# 1-Schematic_picaxe-SMALL.net
KiCad netlist of a schematic drawn in EasyEDA
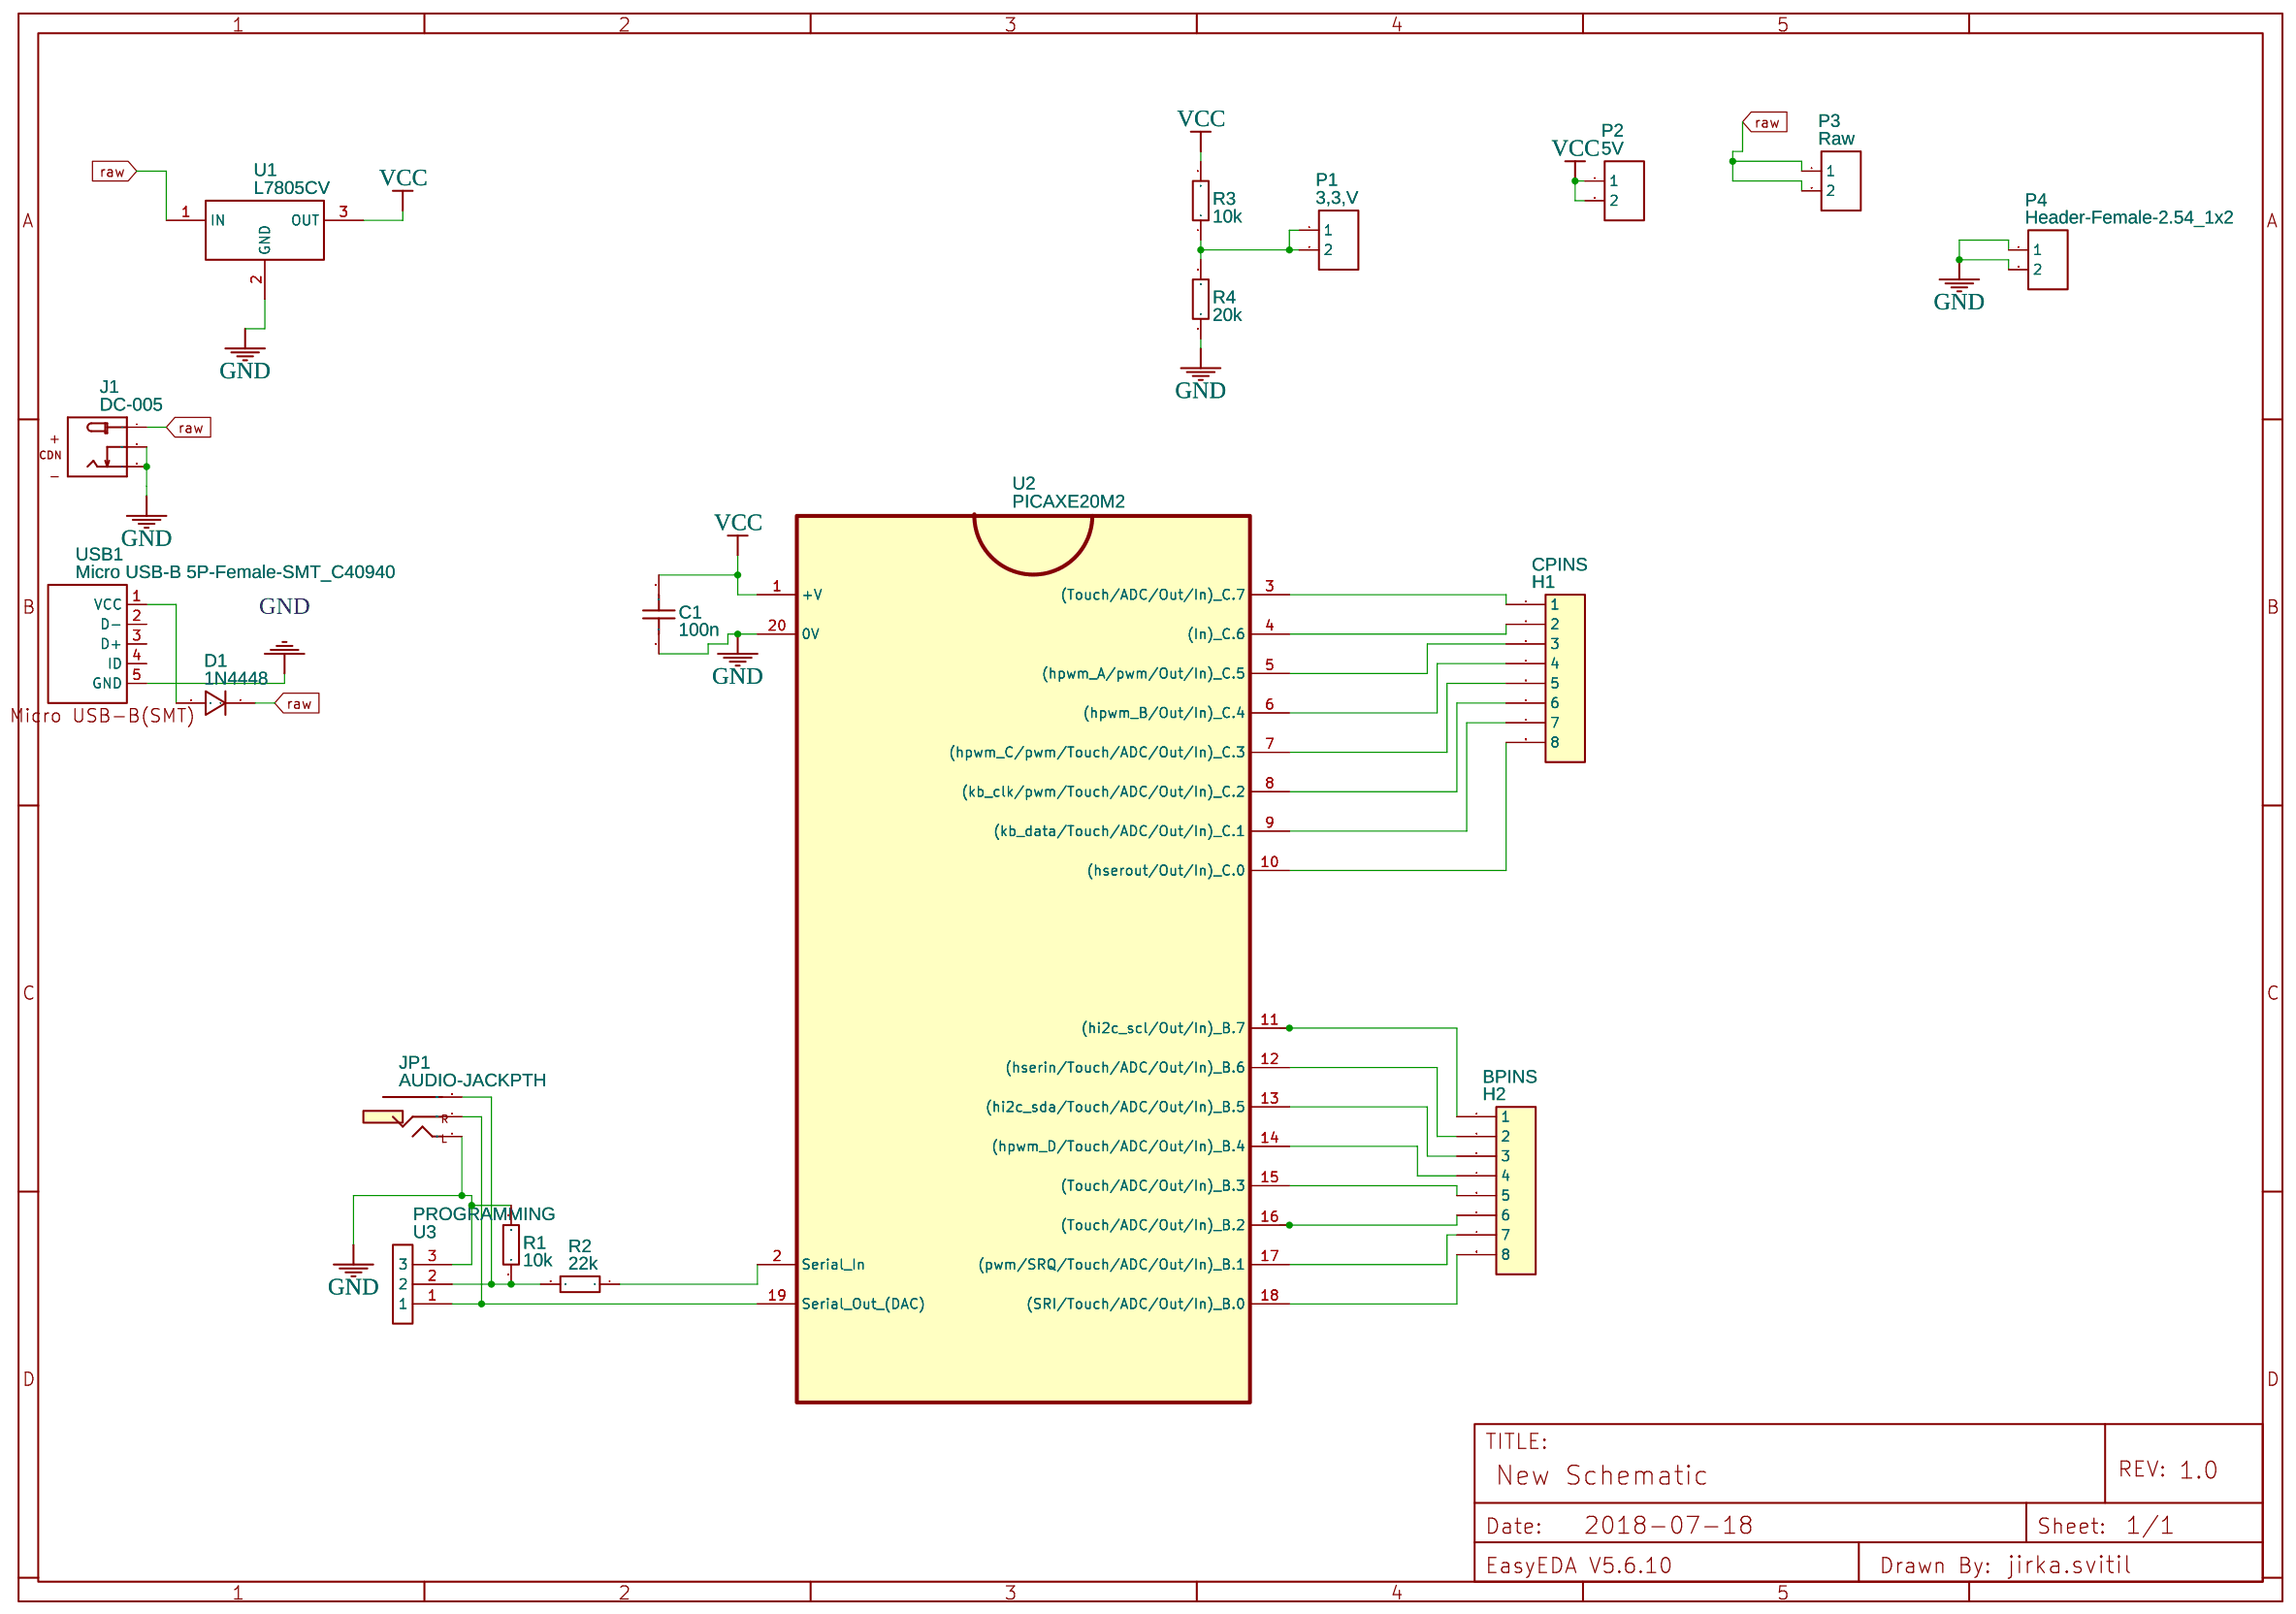
[diagram p0: schematic sheet]

(export (version "E")
  (design (tool "Eeschema 10.0.6"))
  (components
    (comp (ref "BPINS")
      (value "H2")
      (fields (field (name "BOM_Manufacturer Part") "?"))
      (libsource (lib "") (part "Unknown_740_580"))
    )
    (comp (ref "C1")
      (value "100n")
      (fields (field (name "BOM_Manufacturer Part") "?"))
      (libsource (lib "") (part "Cap_RAD-0.1_US"))
    )
    (comp (ref "CPINS")
      (value "H1")
      (fields (field (name "BOM_Manufacturer Part") "?"))
      (libsource (lib "") (part "Unknown_765_320"))
    )
    (comp (ref "D1") (value "1N4448") (libsource (lib "") (part "Unknown_100_350")))
    (comp (ref "J1") (value "DC-005") (libsource (lib "") (part "Unknown_40_220")))
    (comp (ref "JP1")
      (value "AUDIO-JACKPTH")
      (fields (field (name "BOM_Manufacturer Part") "?"))
      (libsource (lib "") (part "Unknown_205_560"))
    )
    (comp (ref "P1")
      (value "3,3,V")
      (fields (field (name "BOM_Manufacturer Part") "2.54-1*2PFemale"))
      (libsource (lib "") (part "Unknown_665_115"))
    )
    (comp (ref "P2")
      (value "5V")
      (fields (field (name "BOM_Manufacturer Part") "2.54-1*2PFemale"))
      (libsource (lib "") (part "Unknown_810_90"))
    )
    (comp (ref "P3")
      (value "Raw")
      (fields (field (name "BOM_Manufacturer Part") "2.54-1*2PFemale"))
      (libsource (lib "") (part "Unknown_920_85"))
    )
    (comp (ref "P4")
      (value "Header-Female-2.54_1x2")
      (fields (field (name "BOM_Manufacturer Part") "2.54-1*2PFemale"))
      (libsource (lib "") (part "Unknown_1025_125"))
    )
    (comp (ref "PROGRAMMING")
      (value "U3")
      (fields (field (name "BOM_Manufacturer Part") "pin 3"))
      (libsource (lib "") (part "Unknown_190_665"))
    )
    (comp (ref "R1")
      (value "10k")
      (fields (field (name "BOM_Manufacturer Part") "?"))
      (libsource (lib "") (part "Res_AXIAL-0.3(1/8W)_EU"))
    )
    (comp (ref "R2")
      (value "22k")
      (fields (field (name "BOM_Manufacturer Part") "?"))
      (libsource (lib "") (part "Res_AXIAL-0.3(1/8W)_EU_1"))
    )
    (comp (ref "R3")
      (value "10k")
      (fields (field (name "BOM_Manufacturer Part") "?"))
      (libsource (lib "") (part "Res_AXIAL-0.3(1/8W)_EU"))
    )
    (comp (ref "R4")
      (value "20k")
      (fields (field (name "BOM_Manufacturer Part") "?"))
      (libsource (lib "") (part "Res_AXIAL-0.3(1/8W)_EU"))
    )
    (comp (ref "U1") (value "L7805CV") (libsource (lib "") (part "Unknown_125_115")))
    (comp (ref "U2")
      (value "PICAXE20M2")
      (fields (field (name "BOM_Manufacturer Part") "PICAXE"))
      (libsource (lib "") (part "Unknown_595_265"))
    )
    (comp (ref "USB1")
      (value "Micro USB-B 5P-Female-SMT_C40940")
      (fields (field (name "BOM_Manufacturer Part") "Micro USB-B 5P-Female-SMT"))
      (libsource (lib "") (part "Unknown_45_320"))
    )
  )
  (nets
    (net (code "1") (name "GND") (class "Default")
      (node (ref "C1") (pin "1") (pinfunction "1_1") (pintype "unspecified"))
      (node (ref "J1") (pin "-1") (pinfunction "-_-1") (pintype "unspecified"))
      (node (ref "J1") (pin "-2") (pinfunction "CDN_-2") (pintype "unspecified"))
      (node (ref "JP1") (pin "2") (pinfunction "LEFT_2") (pintype "unspecified"))
      (node (ref "P4") (pin "1") (pinfunction "1_1") (pintype "input"))
      (node (ref "P4") (pin "2") (pinfunction "2_2") (pintype "input"))
      (node (ref "PROGRAMMING") (pin "3") (pinfunction "3_3") (pintype "unspecified"))
      (node (ref "R1") (pin "2") (pinfunction "2_2") (pintype "unspecified"))
      (node (ref "R4") (pin "1") (pinfunction "1_1") (pintype "unspecified"))
      (node (ref "U1") (pin "2") (pinfunction "GND_2") (pintype "passive"))
      (node (ref "U2") (pin "20") (pinfunction "0V_20") (pintype "unspecified"))
      (node (ref "USB1") (pin "5") (pinfunction "GND_5") (pintype "input"))
    )
    (net (code "2") (name "Net-(D1-A)") (class "Default")
      (node (ref "D1") (pin "1") (pinfunction "A_1") (pintype "unspecified"))
      (node (ref "USB1") (pin "1") (pinfunction "VCC_1") (pintype "input"))
    )
    (net (code "3") (name "Net-(JP1-RIGHT)") (class "Default")
      (node (ref "JP1") (pin "1") (pinfunction "RIGHT_1") (pintype "unspecified"))
      (node (ref "PROGRAMMING") (pin "1") (pinfunction "1_1") (pintype "unspecified"))
      (node (ref "U2") (pin "19") (pinfunction "Serial_Out_(DAC)_19") (pintype "unspecified"))
    )
    (net (code "4") (name "Net-(JP1-SLEEVE)") (class "Default")
      (node (ref "JP1") (pin "0") (pinfunction "SLEEVE_0") (pintype "unspecified"))
      (node (ref "PROGRAMMING") (pin "2") (pinfunction "2_2") (pintype "unspecified"))
      (node (ref "R1") (pin "1") (pinfunction "1_1") (pintype "unspecified"))
      (node (ref "R2") (pin "2") (pinfunction "2_2") (pintype "unspecified"))
    )
    (net (code "5") (name "Net-(P1-Pad1)") (class "Default")
      (node (ref "P1") (pin "1") (pinfunction "1_1") (pintype "input"))
      (node (ref "P1") (pin "2") (pinfunction "2_2") (pintype "input"))
      (node (ref "R3") (pin "1") (pinfunction "1_1") (pintype "unspecified"))
      (node (ref "R4") (pin "2") (pinfunction "2_2") (pintype "unspecified"))
    )
    (net (code "6") (name "Net-(U2-(In)_C.6)") (class "Default")
      (node (ref "CPINS") (pin "2") (pinfunction "2_2") (pintype "input"))
      (node (ref "U2") (pin "4") (pinfunction "(In)_C.6_4") (pintype "unspecified"))
    )
    (net (code "7") (name "Net-(U2-(SRI{slash}Touch{slash}ADC{slash}Out{slash}In)_B.0)") (class "Default")
      (node (ref "BPINS") (pin "8") (pinfunction "8_8") (pintype "input"))
      (node (ref "U2") (pin "18") (pinfunction "(SRI/Touch/ADC/Out/In)_B.0_18") (pintype "unspecified"))
    )
    (net (code "8") (name "Net-(U2-(Touch{slash}ADC{slash}Out{slash}In)_B.2)") (class "Default")
      (node (ref "BPINS") (pin "6") (pinfunction "6_6") (pintype "input"))
      (node (ref "U2") (pin "16") (pinfunction "(Touch/ADC/Out/In)_B.2_16") (pintype "unspecified"))
    )
    (net (code "9") (name "Net-(U2-(Touch{slash}ADC{slash}Out{slash}In)_B.3)") (class "Default")
      (node (ref "BPINS") (pin "5") (pinfunction "5_5") (pintype "input"))
      (node (ref "U2") (pin "15") (pinfunction "(Touch/ADC/Out/In)_B.3_15") (pintype "unspecified"))
    )
    (net (code "10") (name "Net-(U2-(Touch{slash}ADC{slash}Out{slash}In)_C.7)") (class "Default")
      (node (ref "CPINS") (pin "1") (pinfunction "1_1") (pintype "input"))
      (node (ref "U2") (pin "3") (pinfunction "(Touch/ADC/Out/In)_C.7_3") (pintype "unspecified"))
    )
    (net (code "11") (name "Net-(U2-(hi2c_scl{slash}Out{slash}In)_B.7)") (class "Default")
      (node (ref "BPINS") (pin "1") (pinfunction "1_1") (pintype "input"))
      (node (ref "U2") (pin "11") (pinfunction "(hi2c_scl/Out/In)_B.7_11") (pintype "unspecified"))
    )
    (net (code "12") (name "Net-(U2-(hi2c_sda{slash}Touch{slash}ADC{slash}Out{slash}In)_B.5)") (class "Default")
      (node (ref "BPINS") (pin "3") (pinfunction "3_3") (pintype "input"))
      (node (ref "U2") (pin "13") (pinfunction "(hi2c_sda/Touch/ADC/Out/In)_B.5_13") (pintype "unspecified"))
    )
    (net (code "13") (name "Net-(U2-(hpwm_A{slash}pwm{slash}Out{slash}In)_C.5)") (class "Default")
      (node (ref "CPINS") (pin "3") (pinfunction "3_3") (pintype "input"))
      (node (ref "U2") (pin "5") (pinfunction "(hpwm_A/pwm/Out/In)_C.5_5") (pintype "unspecified"))
    )
    (net (code "14") (name "Net-(U2-(hpwm_B{slash}Out{slash}In)_C.4)") (class "Default")
      (node (ref "CPINS") (pin "4") (pinfunction "4_4") (pintype "input"))
      (node (ref "U2") (pin "6") (pinfunction "(hpwm_B/Out/In)_C.4_6") (pintype "unspecified"))
    )
    (net (code "15") (name "Net-(U2-(hpwm_C{slash}pwm{slash}Touch{slash}ADC{slash}Out{slash}In)_C.3)") (class "Default")
      (node (ref "CPINS") (pin "5") (pinfunction "5_5") (pintype "input"))
      (node (ref "U2") (pin "7") (pinfunction "(hpwm_C/pwm/Touch/ADC/Out/In)_C.3_7") (pintype "unspecified"))
    )
    (net (code "16") (name "Net-(U2-(hpwm_D{slash}Touch{slash}ADC{slash}Out{slash}In)_B.4)") (class "Default")
      (node (ref "BPINS") (pin "4") (pinfunction "4_4") (pintype "input"))
      (node (ref "U2") (pin "14") (pinfunction "(hpwm_D/Touch/ADC/Out/In)_B.4_14") (pintype "unspecified"))
    )
    (net (code "17") (name "Net-(U2-(hserin{slash}Touch{slash}ADC{slash}Out{slash}In)_B.6)") (class "Default")
      (node (ref "BPINS") (pin "2") (pinfunction "2_2") (pintype "input"))
      (node (ref "U2") (pin "12") (pinfunction "(hserin/Touch/ADC/Out/In)_B.6_12") (pintype "unspecified"))
    )
    (net (code "18") (name "Net-(U2-(hserout{slash}Out{slash}In)_C.0)") (class "Default")
      (node (ref "CPINS") (pin "8") (pinfunction "8_8") (pintype "input"))
      (node (ref "U2") (pin "10") (pinfunction "(hserout/Out/In)_C.0_10") (pintype "unspecified"))
    )
    (net (code "19") (name "Net-(U2-(kb_clk{slash}pwm{slash}Touch{slash}ADC{slash}Out{slash}In)_C.2)") (class "Default")
      (node (ref "CPINS") (pin "6") (pinfunction "6_6") (pintype "input"))
      (node (ref "U2") (pin "8") (pinfunction "(kb_clk/pwm/Touch/ADC/Out/In)_C.2_8") (pintype "unspecified"))
    )
    (net (code "20") (name "Net-(U2-(kb_data{slash}Touch{slash}ADC{slash}Out{slash}In)_C.1)") (class "Default")
      (node (ref "CPINS") (pin "7") (pinfunction "7_7") (pintype "input"))
      (node (ref "U2") (pin "9") (pinfunction "(kb_data/Touch/ADC/Out/In)_C.1_9") (pintype "unspecified"))
    )
    (net (code "21") (name "Net-(U2-(pwm{slash}SRQ{slash}Touch{slash}ADC{slash}Out{slash}In)_B.1)") (class "Default")
      (node (ref "BPINS") (pin "7") (pinfunction "7_7") (pintype "input"))
      (node (ref "U2") (pin "17") (pinfunction "(pwm/SRQ/Touch/ADC/Out/In)_B.1_17") (pintype "unspecified"))
    )
    (net (code "22") (name "Net-(U2-Serial_In)") (class "Default")
      (node (ref "R2") (pin "1") (pinfunction "1_1") (pintype "unspecified"))
      (node (ref "U2") (pin "2") (pinfunction "Serial_In_2") (pintype "unspecified"))
    )
    (net (code "23") (name "VCC") (class "Default")
      (node (ref "C1") (pin "2") (pinfunction "2_2") (pintype "unspecified"))
      (node (ref "P2") (pin "1") (pinfunction "1_1") (pintype "input"))
      (node (ref "P2") (pin "2") (pinfunction "2_2") (pintype "input"))
      (node (ref "R3") (pin "2") (pinfunction "2_2") (pintype "unspecified"))
      (node (ref "U1") (pin "3") (pinfunction "OUT_3") (pintype "passive"))
      (node (ref "U2") (pin "1") (pinfunction "+V_1") (pintype "unspecified"))
    )
    (net (code "24") (name "raw") (class "Default")
      (node (ref "D1") (pin "2") (pinfunction "K_2") (pintype "unspecified"))
      (node (ref "J1") (pin "+") (pinfunction "+_+") (pintype "unspecified"))
      (node (ref "P3") (pin "1") (pinfunction "1_1") (pintype "input"))
      (node (ref "P3") (pin "2") (pinfunction "2_2") (pintype "input"))
      (node (ref "U1") (pin "1") (pinfunction "IN_1") (pintype "passive"))
    )
    (net (code "25") (name "unconnected-(USB1-D+-Pad3)") (class "Default")
      (node (ref "USB1") (pin "3") (pinfunction "D+_3") (pintype "input"))
    )
    (net (code "26") (name "unconnected-(USB1-D--Pad2)") (class "Default")
      (node (ref "USB1") (pin "2") (pinfunction "D-_2") (pintype "input"))
    )
    (net (code "27") (name "unconnected-(USB1-ID-Pad4)") (class "Default")
      (node (ref "USB1") (pin "4") (pinfunction "ID_4") (pintype "input"))
    )
  )
)
